# ShineSensor.net
KiCad netlist of a schematic drawn in EAGLE
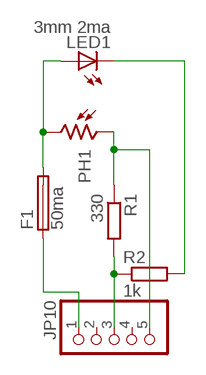
[diagram p0: schematic, sheet 1]

(export (version "E")
  (design (tool "Eeschema 10.0.6"))
  (components
    (comp (ref "F1")
      (value "50ma")
      (footprint "eagle-import:MF-SMDF050")
      (libsource (lib "eagle-import") (part "MF-SMDF050"))
    )
    (comp (ref "JP10")
      (value "PINHD-1X5")
      (footprint "eagle-import:1X05")
      (libsource (lib "eagle-import") (part "PINHD-1X5"))
    )
    (comp (ref "LED1")
      (value "3mm 2ma")
      (footprint "eagle-import:LED3MM")
      (fields (field (name "MF") "VISHAY SEMICONDUCTOR"))
      (libsource (lib "eagle-import") (part "TLLY4400"))
    )
    (comp (ref "PH1")
      (value "B1060_23")
      (footprint "eagle-import:TO-8_B10")
      (libsource (lib "eagle-import") (part "?1060B_23"))
    )
    (comp (ref "R1")
      (value "330")
      (footprint "eagle-import:R1206")
      (libsource (lib "eagle-import") (part "R-EU_R1206"))
    )
    (comp (ref "R2")
      (value "1k")
      (footprint "eagle-import:R1206")
      (libsource (lib "eagle-import") (part "R-EU_R1206"))
    )
  )
  (nets
    (net (code "1") (name "Net-(F1-Pad1)") (class "Default")
      (node (ref "F1") (pin "1") (pinfunction "1_1") (pintype "passive"))
      (node (ref "JP10") (pin "1") (pinfunction "1_1") (pintype "passive"))
    )
    (net (code "2") (name "Net-(F1-Pad2)") (class "Default")
      (node (ref "F1") (pin "2") (pinfunction "2_2") (pintype "passive"))
      (node (ref "LED1") (pin "A") (pinfunction "A_A") (pintype "passive"))
      (node (ref "PH1") (pin "2") (pinfunction "2_2") (pintype "passive"))
    )
    (net (code "3") (name "Net-(JP10-Pad3)") (class "Default")
      (node (ref "JP10") (pin "3") (pinfunction "3_3") (pintype "passive"))
      (node (ref "R1") (pin "2") (pinfunction "2_2") (pintype "passive"))
      (node (ref "R2") (pin "1") (pinfunction "1_1") (pintype "passive"))
    )
    (net (code "4") (name "Net-(JP10-Pad5)") (class "Default")
      (node (ref "JP10") (pin "5") (pinfunction "5_5") (pintype "passive"))
      (node (ref "PH1") (pin "1") (pinfunction "1_1") (pintype "passive"))
      (node (ref "R1") (pin "1") (pinfunction "1_1") (pintype "passive"))
    )
    (net (code "5") (name "Net-(LED1-C)") (class "Default")
      (node (ref "LED1") (pin "K") (pinfunction "C_K") (pintype "passive"))
      (node (ref "R2") (pin "2") (pinfunction "2_2") (pintype "passive"))
    )
    (net (code "6") (name "unconnected-(JP10-Pad2)") (class "Default")
      (node (ref "JP10") (pin "2") (pinfunction "2_2") (pintype "passive"))
    )
    (net (code "7") (name "unconnected-(JP10-Pad4)") (class "Default")
      (node (ref "JP10") (pin "4") (pinfunction "4_4") (pintype "passive"))
    )
  )
)
